# Kasli-SOC_MUX_I2C.net
KiCad netlist of a schematic drawn in Altium Designer
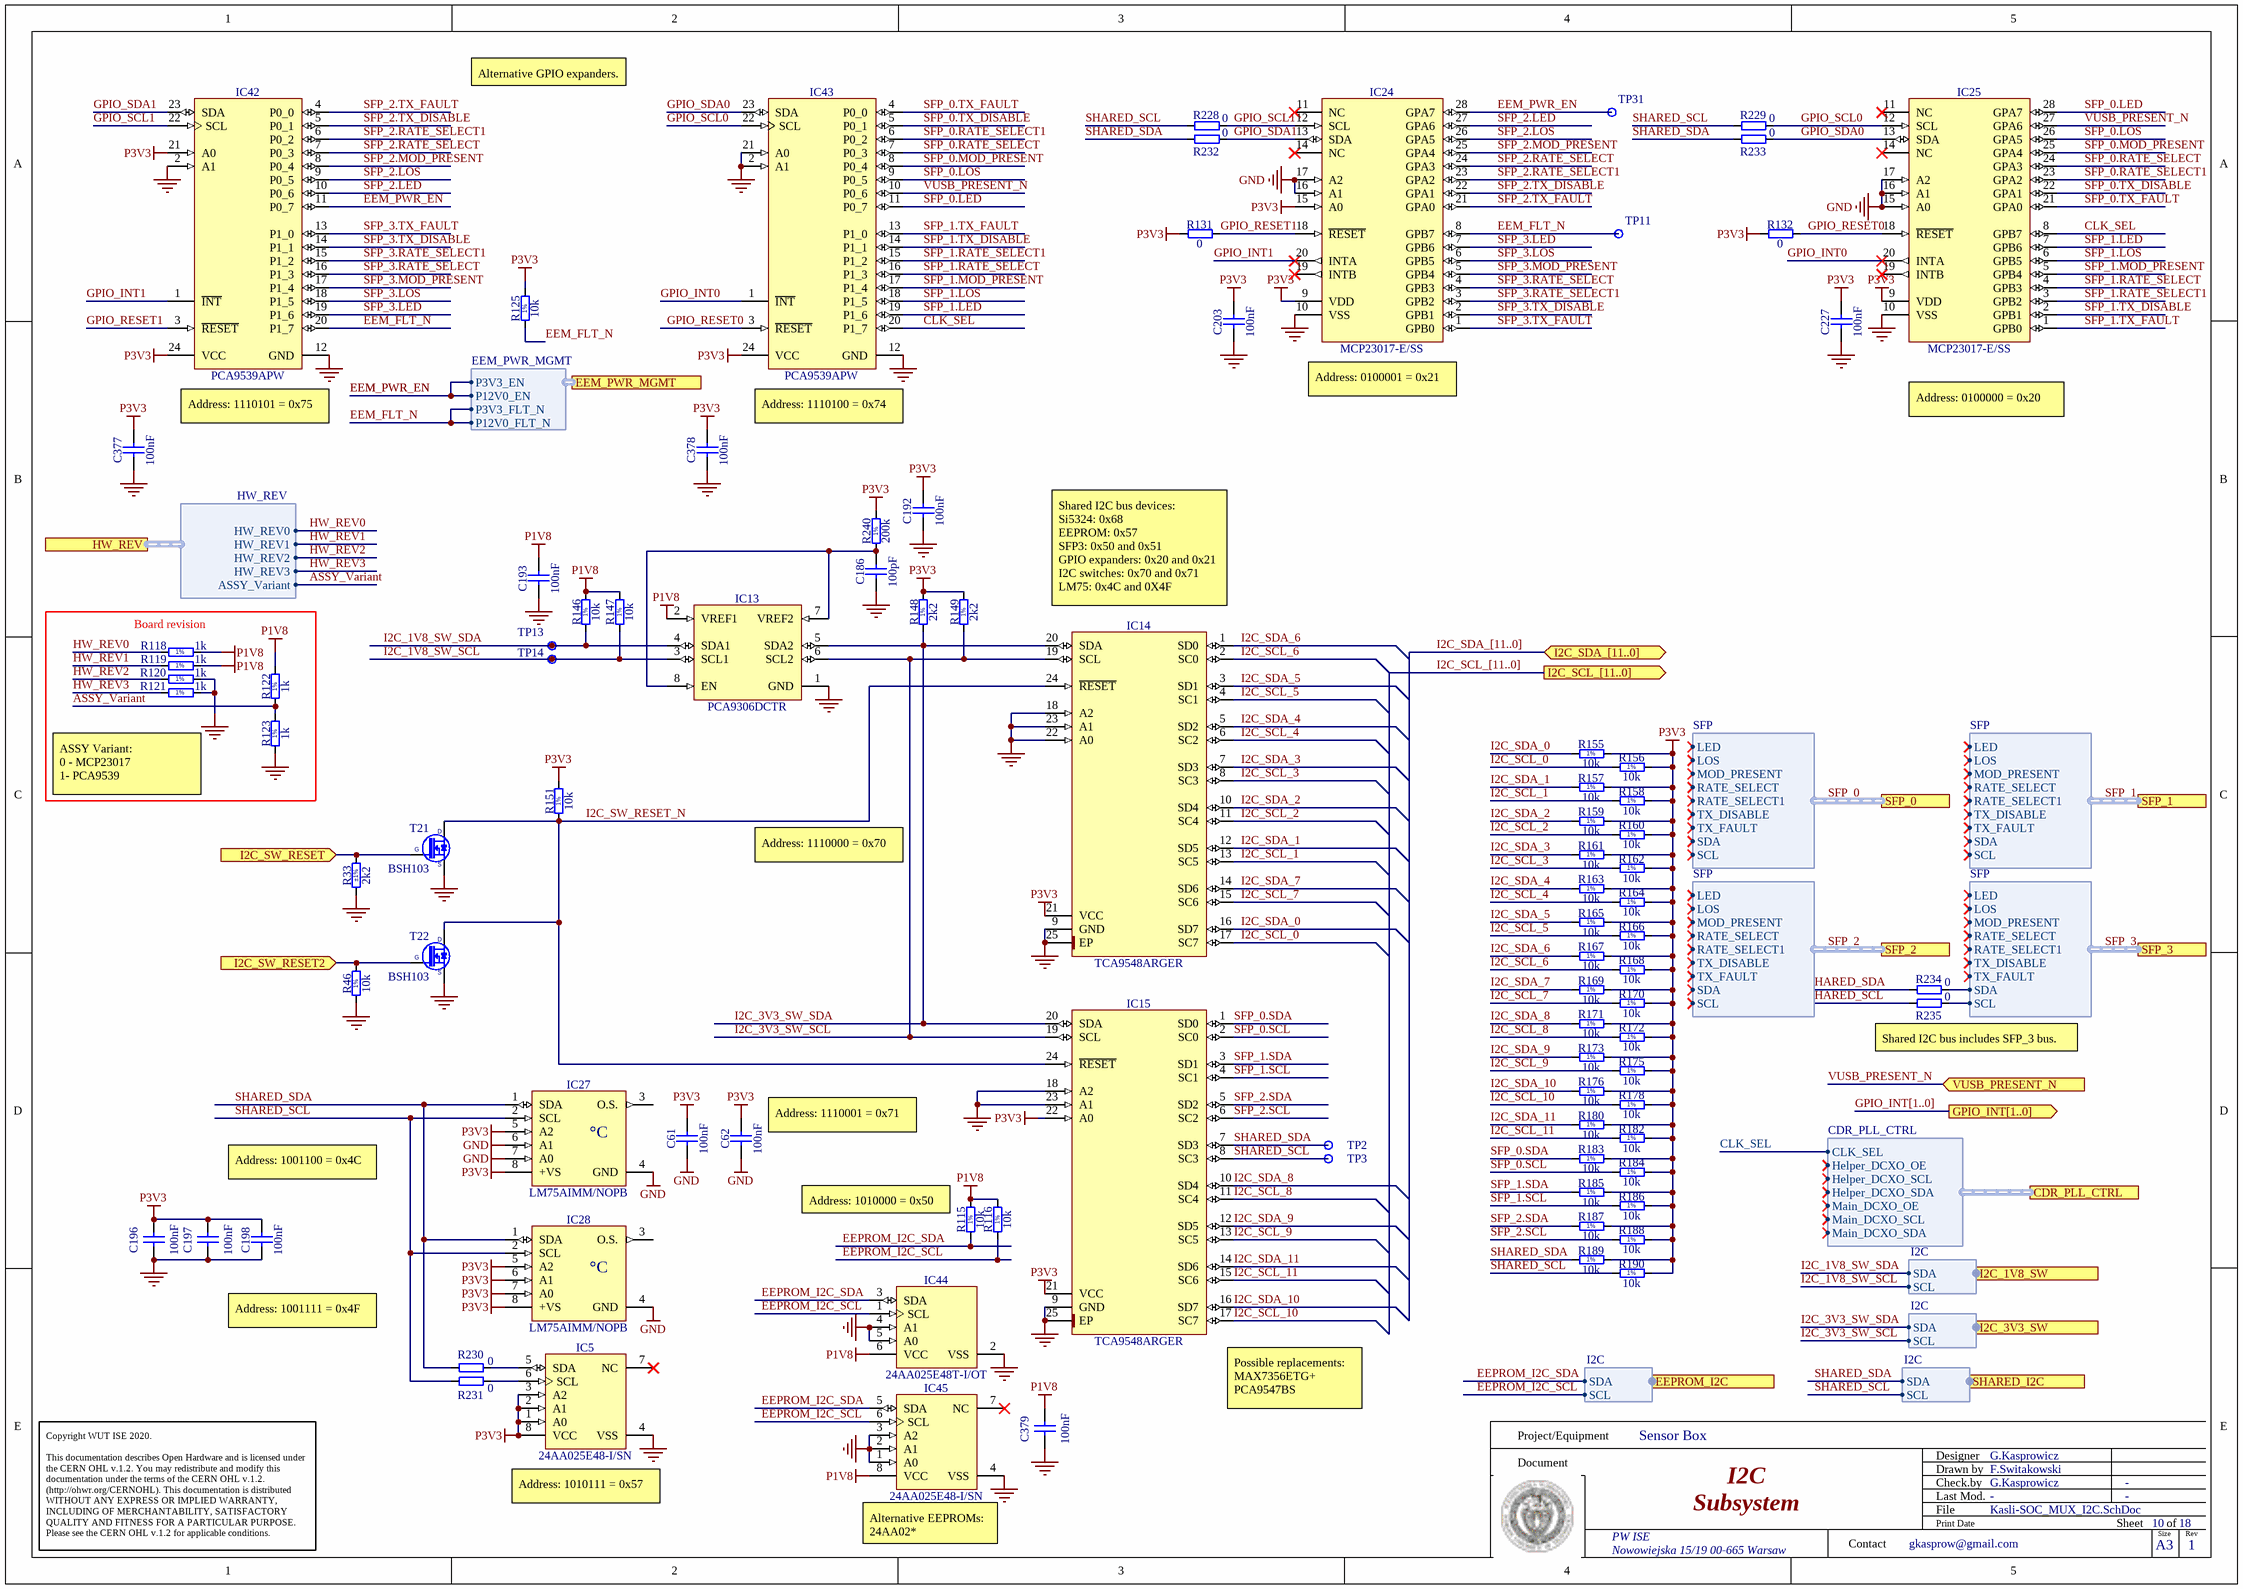
[diagram p0: Kasli-SOC_MUX_I2C.SchDoc]

(export (version "E")
  (design (tool "Eeschema 10.0.6"))
  (components
    (comp (ref "C61")
      (value "100nF")
      (footprint "CAPC1005X55N")
      (description "Non-polarised capacitor")
      (fields
        (field (name "PART NUMBER") "CC0402_100NF_16V_10%_X7R")
        (field (name "VOLTAGE") "16V")
        (field (name "AUTHOR") "CERN DEM JLC")
      )
      (libsource (lib "Capacitors") (part "Capacitor - non polarized"))
    )
    (comp (ref "C62")
      (value "100nF")
      (footprint "CAPC1005X55N")
      (description "Non-polarised capacitor")
      (fields
        (field (name "PART NUMBER") "CC0402_100NF_16V_10%_X7R")
        (field (name "VOLTAGE") "16V")
        (field (name "AUTHOR") "CERN DEM JLC")
      )
      (libsource (lib "Capacitors") (part "Capacitor - non polarized"))
    )
    (comp (ref "C186")
      (value "100pF")
      (footprint "CAPC1005X55N")
      (description "Non-polarised capacitor")
      (fields
        (field (name "PART NUMBER") "CC0402_100PF_50V_5%_C0G")
        (field (name "VOLTAGE") "50V")
        (field (name "AUTHOR") "CERN DEM JLC")
      )
      (libsource (lib "Capacitors") (part "Capacitor - non polarized"))
    )
    (comp (ref "C192")
      (value "100nF")
      (footprint "CAPC1005X55N")
      (description "Non-polarised capacitor")
      (fields
        (field (name "PART NUMBER") "CC0402_100NF_16V_10%_X7R")
        (field (name "VOLTAGE") "16V")
        (field (name "AUTHOR") "CERN DEM JLC")
      )
      (libsource (lib "Capacitors") (part "Capacitor - non polarized"))
    )
    (comp (ref "C193")
      (value "100nF")
      (footprint "CAPC1005X55N")
      (description "Non-polarised capacitor")
      (fields
        (field (name "PART NUMBER") "CC0402_100NF_16V_10%_X7R")
        (field (name "VOLTAGE") "16V")
        (field (name "AUTHOR") "CERN DEM JLC")
      )
      (libsource (lib "Capacitors") (part "Capacitor - non polarized"))
    )
    (comp (ref "C196")
      (value "100nF")
      (footprint "CAPC0603X33N")
      (description "Non-polarised capacitor")
      (fields
        (field (name "PART NUMBER") "CC0201_100NF_6.3V_10%_X5R")
        (field (name "VOLTAGE") "6.3V")
        (field (name "AUTHOR") "CERN DEM JLC")
      )
      (libsource (lib "Capacitors") (part "Capacitor - non polarized"))
    )
    (comp (ref "C197")
      (value "100nF")
      (footprint "CAPC0603X33N")
      (description "Non-polarised capacitor")
      (fields
        (field (name "PART NUMBER") "CC0201_100NF_6.3V_10%_X5R")
        (field (name "VOLTAGE") "6.3V")
        (field (name "AUTHOR") "CERN DEM JLC")
      )
      (libsource (lib "Capacitors") (part "Capacitor - non polarized"))
    )
    (comp (ref "C198")
      (value "100nF")
      (footprint "CAPC1005X55N")
      (description "Non-polarised capacitor")
      (fields
        (field (name "PART NUMBER") "CC0402_100NF_16V_10%_X7R")
        (field (name "VOLTAGE") "16V")
        (field (name "AUTHOR") "CERN DEM JLC")
      )
      (libsource (lib "Capacitors") (part "Capacitor - non polarized"))
    )
    (comp (ref "C203")
      (value "100nF")
      (footprint "CAPC1005X55N")
      (description "Non-polarised capacitor")
      (fields
        (field (name "PART NUMBER") "CC0402_100NF_16V_10%_X7R")
        (field (name "VOLTAGE") "16V")
        (field (name "AUTHOR") "CERN DEM JLC")
      )
      (libsource (lib "Capacitors") (part "Capacitor - non polarized"))
    )
    (comp (ref "C227")
      (value "100nF")
      (footprint "CAPC1005X55N")
      (description "Non-polarised capacitor")
      (fields
        (field (name "PART NUMBER") "CC0402_100NF_16V_10%_X7R")
        (field (name "VOLTAGE") "16V")
        (field (name "AUTHOR") "CERN DEM JLC")
      )
      (libsource (lib "Capacitors") (part "Capacitor - non polarized"))
    )
    (comp (ref "C377")
      (value "100nF")
      (footprint "CAPC1005X55N")
      (description "Non-polarised capacitor")
      (fields
        (field (name "PART NUMBER") "CC0402_100NF_16V_10%_X7R")
        (field (name "VOLTAGE") "16V")
        (field (name "AUTHOR") "CERN DEM JLC")
      )
      (libsource (lib "Capacitors") (part "Capacitor - non polarized"))
    )
    (comp (ref "C378")
      (value "100nF")
      (footprint "CAPC1005X55N")
      (description "Non-polarised capacitor")
      (fields
        (field (name "PART NUMBER") "CC0402_100NF_16V_10%_X7R")
        (field (name "VOLTAGE") "16V")
        (field (name "AUTHOR") "CERN DEM JLC")
      )
      (libsource (lib "Capacitors") (part "Capacitor - non polarized"))
    )
    (comp (ref "C379")
      (value "100nF")
      (footprint "CAPC1005X55N")
      (description "Non-polarised capacitor")
      (fields
        (field (name "PART NUMBER") "CC0402_100NF_16V_10%_X5R")
        (field (name "VOLTAGE") "16V")
        (field (name "AUTHOR") "CERN DEM JLC")
      )
      (libsource (lib "Capacitors") (part "Capacitor - non polarized"))
    )
    (comp (ref "IC5")
      (value "24AA025E48-I/SN")
      (footprint "SOIC127P600X175-8N")
      (description "1.7V-5.5V, 2K I2C™ Serial EEPROMs with EUI-48™ Node Identity")
      (fields (field (name "MANUFACTURER") "MICROCHIP TECHNOLOGY") (field (name "AUTHOR") "CERN DEM MR"))
      (libsource (lib "ICs And Semiconductors") (part "24AA025E48-I/SN"))
    )
    (comp (ref "IC13")
      (value "PCA9306DCTR")
      (footprint "SOP65P400X130-8N")
      (description "Dual Bidirectional I2C Bus And SMBus Voltage-Level Translator")
      (fields (field (name "MANUFACTURER") "TEXAS INSTRUMENTS") (field (name "AUTHOR") "CERN DEM JLC"))
      (libsource (lib "ICs And Semiconductors") (part "PCA9306D"))
    )
    (comp (ref "IC14")
      (value "TCA9548ARGER")
      (footprint "QFN50P400X400X100-25N-S220")
      (description "Low Voltage 8-Channel I2C Switch With Reset")
      (fields (field (name "MANUFACTURER") "TEXAS INSTRUMENTS") (field (name "AUTHOR") "CERN DEM JLC"))
      (libsource (lib "ICs And Semiconductors") (part "TCA9548ARGER"))
    )
    (comp (ref "IC15")
      (value "TCA9548ARGER")
      (footprint "QFN50P400X400X100-25N-S220")
      (description "Low Voltage 8-Channel I2C Switch With Reset")
      (fields (field (name "MANUFACTURER") "TEXAS INSTRUMENTS") (field (name "AUTHOR") "CERN DEM JLC"))
      (libsource (lib "ICs And Semiconductors") (part "TCA9548ARGER"))
    )
    (comp (ref "IC24")
      (value "MCP23017-E/SS")
      (footprint "SOP65P780X200-28N")
      (description "16-bit I/O Port Expander With Serial Interface")
      (fields (field (name "MANUFACTURER") "MICROCHIP TECHNOLOGY") (field (name "AUTHOR") "CERN DEM JLC"))
      (libsource (lib "ICs And Semiconductors") (part "MCP23017-E/SS"))
    )
    (comp (ref "IC25")
      (value "MCP23017-E/SS")
      (footprint "SOP65P780X200-28N")
      (description "16-bit I/O Port Expander With Serial Interface")
      (fields (field (name "MANUFACTURER") "MICROCHIP TECHNOLOGY") (field (name "AUTHOR") "CERN DEM JLC"))
      (libsource (lib "ICs And Semiconductors") (part "MCP23017-E/SS"))
    )
    (comp (ref "IC27")
      (value "LM75AIMM/NOPB")
      (footprint "SOP65P490X109-8N")
      (description "Digital Temperature Sensor and Thermal Watchdog with Two-Wire Interface")
      (fields (field (name "MANUFACTURER") "TEXAS INSTRUMENTS") (field (name "AUTHOR") "CERN DEM JLC"))
      (libsource (lib "ICs And Semiconductors") (part "LM75"))
    )
    (comp (ref "IC28")
      (value "LM75AIMM/NOPB")
      (footprint "SOP65P490X109-8N")
      (description "Digital Temperature Sensor and Thermal Watchdog with Two-Wire Interface")
      (fields (field (name "MANUFACTURER") "TEXAS INSTRUMENTS") (field (name "AUTHOR") "CERN DEM JLC"))
      (libsource (lib "ICs And Semiconductors") (part "LM75"))
    )
    (comp (ref "IC42")
      (value "PCA9539APW")
      (footprint "SOP65P640X110-24N")
      (description "Low-Voltage 16-Bit I2C-Bus I/O Port with Interrupt and Reset")
      (fields (field (name "MANUFACTURER") "NXP SEMICONDUCTORS") (field (name "AUTHOR") "CERN DEM JMW"))
      (libsource (lib "ICs And Semiconductors") (part "PCA9539APW"))
    )
    (comp (ref "IC43")
      (value "PCA9539APW")
      (footprint "SOP65P640X110-24N")
      (description "Low-Voltage 16-Bit I2C-Bus I/O Port with Interrupt and Reset")
      (fields (field (name "MANUFACTURER") "NXP SEMICONDUCTORS") (field (name "AUTHOR") "CERN DEM JMW"))
      (libsource (lib "ICs And Semiconductors") (part "PCA9539APW"))
    )
    (comp (ref "IC44")
      (value "24AA025E48T-I/OT")
      (footprint "SOT95P280X145-6N")
      (description "1.7V-5.5V, 2K I2C Serial EEPROM With EUI-48 Node Identity")
      (fields (field (name "MANUFACTURER") "MICROCHIP TECHNOLOGY") (field (name "AUTHOR") "CERN DEM BC"))
      (libsource (lib "ICs And Semiconductors") (part "24AA025E48T-I/OT"))
    )
    (comp (ref "IC45")
      (value "24AA025E48-I/SN")
      (footprint "SOIC127P600X175-8N")
      (description "1.7V-5.5V, 2K I2C™ Serial EEPROMs with EUI-48™ Node Identity")
      (fields (field (name "MANUFACTURER") "MICROCHIP TECHNOLOGY") (field (name "AUTHOR") "CERN DEM MR"))
      (libsource (lib "ICs And Semiconductors") (part "24AA025E48-I/SN"))
    )
    (comp (ref "R33")
      (value "2k2")
      (footprint "RESC1005X40N")
      (description "Resistor - 1%")
      (fields
        (field (name "TOLERANCE") "±1%")
        (field (name "PART NUMBER") "R0402_2K2_1%_0.0625W_100PPM")
        (field (name "POWER") "0.0625W")
        (field (name "AUTHOR") "CERN DEM JLC")
      )
      (libsource (lib "Resistors") (part "Resistor - 1%"))
    )
    (comp (ref "R46")
      (value "10k")
      (footprint "RESC1005X40N")
      (description "Resistor - 1%")
      (fields
        (field (name "PART NUMBER") "R0402_10K_1%_0.0625W_100PPM")
        (field (name "POWER") "0.0625W")
        (field (name "AUTHOR") "CERN DEM JLC")
      )
      (libsource (lib "Resistors") (part "Resistor - 1%"))
    )
    (comp (ref "R115")
      (value "10k")
      (footprint "RESC1005X40N")
      (description "Resistor - 1%")
      (fields
        (field (name "PART NUMBER") "R0402_10K_1%_0.0625W_100PPM")
        (field (name "POWER") "0.0625W")
        (field (name "AUTHOR") "CERN DEM JLC")
      )
      (libsource (lib "Resistors") (part "Resistor - 1%"))
    )
    (comp (ref "R116")
      (value "10k")
      (footprint "RESC1005X40N")
      (description "Resistor - 1%")
      (fields
        (field (name "PART NUMBER") "R0402_10K_1%_0.0625W_100PPM")
        (field (name "POWER") "0.0625W")
        (field (name "AUTHOR") "CERN DEM JLC")
      )
      (libsource (lib "Resistors") (part "Resistor - 1%"))
    )
    (comp (ref "R118")
      (value "1k")
      (footprint "RESC1005X40N")
      (description "Resistor - 1%")
      (fields
        (field (name "PART NUMBER") "R0402_1K_1%_0.0625W_100PPM")
        (field (name "POWER") "0.0625W")
        (field (name "AUTHOR") "CERN DEM JLC")
      )
      (libsource (lib "Resistors") (part "Resistor - 1%"))
    )
    (comp (ref "R119")
      (value "1k")
      (footprint "RESC1005X40N")
      (description "Resistor - 1%")
      (fields
        (field (name "PART NUMBER") "R0402_1K_1%_0.0625W_100PPM")
        (field (name "POWER") "0.0625W")
        (field (name "AUTHOR") "CERN DEM JLC")
      )
      (libsource (lib "Resistors") (part "Resistor - 1%"))
    )
    (comp (ref "R120")
      (value "1k")
      (footprint "RESC1005X40N")
      (description "Resistor - 1%")
      (fields
        (field (name "PART NUMBER") "R0402_1K_1%_0.0625W_100PPM")
        (field (name "POWER") "0.0625W")
        (field (name "AUTHOR") "CERN DEM JLC")
      )
      (libsource (lib "Resistors") (part "Resistor - 1%"))
    )
    (comp (ref "R121")
      (value "1k")
      (footprint "RESC1005X40N")
      (description "Resistor - 1%")
      (fields
        (field (name "PART NUMBER") "R0402_1K_1%_0.0625W_100PPM")
        (field (name "POWER") "0.0625W")
        (field (name "AUTHOR") "CERN DEM JLC")
      )
      (libsource (lib "Resistors") (part "Resistor - 1%"))
    )
    (comp (ref "R122")
      (value "1k")
      (footprint "RESC1005X40N")
      (description "Resistor - 1%")
      (fields
        (field (name "PART NUMBER") "R0402_1K_1%_0.0625W_100PPM")
        (field (name "POWER") "0.0625W")
        (field (name "AUTHOR") "CERN DEM JLC")
      )
      (libsource (lib "Resistors") (part "Resistor - 1%"))
    )
    (comp (ref "R123")
      (value "1k")
      (footprint "RESC1005X40N")
      (description "Resistor - 1%")
      (fields
        (field (name "PART NUMBER") "R0402_1K_1%_0.0625W_100PPM")
        (field (name "POWER") "0.0625W")
        (field (name "AUTHOR") "CERN DEM JLC")
      )
      (libsource (lib "Resistors") (part "Resistor - 1%"))
    )
    (comp (ref "R125")
      (value "10k")
      (footprint "RESC1005X40N")
      (description "Resistor - 1%")
      (fields
        (field (name "PART NUMBER") "R0402_10K_1%_0.0625W_100PPM")
        (field (name "POWER") "0.0625W")
        (field (name "AUTHOR") "CERN DEM JLC")
      )
      (libsource (lib "Resistors") (part "Resistor - 1%"))
    )
    (comp (ref "R131")
      (value "0")
      (footprint "RESC1005X40N")
      (description "Resistor")
      (fields
        (field (name "PART NUMBER") "R0402_0R_JUMPER")
        (field (name "MANUFACTURER") "GENERIC")
        (field (name "AUTHOR") "CERN DEM JLC")
      )
      (libsource (lib "Resistors") (part "Resistor"))
    )
    (comp (ref "R132")
      (value "0")
      (footprint "RESC1005X40N")
      (description "Resistor")
      (fields
        (field (name "PART NUMBER") "R0402_0R_JUMPER")
        (field (name "MANUFACTURER") "GENERIC")
        (field (name "AUTHOR") "CERN DEM JLC")
      )
      (libsource (lib "Resistors") (part "Resistor"))
    )
    (comp (ref "R146")
      (value "10k")
      (footprint "RESC1005X40N")
      (description "Resistor - 1%")
      (fields
        (field (name "PART NUMBER") "R0402_10K_1%_0.0625W_100PPM")
        (field (name "POWER") "0.0625W")
        (field (name "AUTHOR") "CERN DEM JLC")
      )
      (libsource (lib "Resistors") (part "Resistor - 1%"))
    )
    (comp (ref "R147")
      (value "10k")
      (footprint "RESC1005X40N")
      (description "Resistor - 1%")
      (fields
        (field (name "PART NUMBER") "R0402_10K_1%_0.0625W_100PPM")
        (field (name "POWER") "0.0625W")
        (field (name "AUTHOR") "CERN DEM JLC")
      )
      (libsource (lib "Resistors") (part "Resistor - 1%"))
    )
    (comp (ref "R148")
      (value "2k2")
      (footprint "RESC1005X40N")
      (description "Resistor - 1%")
      (fields
        (field (name "PART NUMBER") "R0402_2K2_1%_0.0625W_100PPM")
        (field (name "POWER") "0.0625W")
        (field (name "AUTHOR") "CERN DEM JLC")
      )
      (libsource (lib "Resistors") (part "Resistor - 1%"))
    )
    (comp (ref "R149")
      (value "2k2")
      (footprint "RESC1005X40N")
      (description "Resistor - 1%")
      (fields
        (field (name "PART NUMBER") "R0402_2K2_1%_0.0625W_100PPM")
        (field (name "POWER") "0.0625W")
        (field (name "AUTHOR") "CERN DEM JLC")
      )
      (libsource (lib "Resistors") (part "Resistor - 1%"))
    )
    (comp (ref "R151")
      (value "10k")
      (footprint "RESC1005X40N")
      (description "Resistor - 1%")
      (fields
        (field (name "PART NUMBER") "R0402_10K_1%_0.0625W_100PPM")
        (field (name "POWER") "0.0625W")
        (field (name "AUTHOR") "CERN DEM JLC")
      )
      (libsource (lib "Resistors") (part "Resistor - 1%"))
    )
    (comp (ref "R155")
      (value "10k")
      (footprint "RESC1005X40N")
      (description "Resistor - 1%")
      (fields
        (field (name "PART NUMBER") "R0402_10K_1%_0.0625W_100PPM")
        (field (name "POWER") "0.0625W")
        (field (name "AUTHOR") "CERN DEM JLC")
      )
      (libsource (lib "Resistors") (part "Resistor - 1%"))
    )
    (comp (ref "R156")
      (value "10k")
      (footprint "RESC1005X40N")
      (description "Resistor - 1%")
      (fields
        (field (name "PART NUMBER") "R0402_10K_1%_0.0625W_100PPM")
        (field (name "POWER") "0.0625W")
        (field (name "AUTHOR") "CERN DEM JLC")
      )
      (libsource (lib "Resistors") (part "Resistor - 1%"))
    )
    (comp (ref "R157")
      (value "10k")
      (footprint "RESC1005X40N")
      (description "Resistor - 1%")
      (fields
        (field (name "PART NUMBER") "R0402_10K_1%_0.0625W_100PPM")
        (field (name "POWER") "0.0625W")
        (field (name "AUTHOR") "CERN DEM JLC")
      )
      (libsource (lib "Resistors") (part "Resistor - 1%"))
    )
    (comp (ref "R158")
      (value "10k")
      (footprint "RESC1005X40N")
      (description "Resistor - 1%")
      (fields
        (field (name "PART NUMBER") "R0402_10K_1%_0.0625W_100PPM")
        (field (name "POWER") "0.0625W")
        (field (name "AUTHOR") "CERN DEM JLC")
      )
      (libsource (lib "Resistors") (part "Resistor - 1%"))
    )
    (comp (ref "R159")
      (value "10k")
      (footprint "RESC1005X40N")
      (description "Resistor - 1%")
      (fields
        (field (name "PART NUMBER") "R0402_10K_1%_0.0625W_100PPM")
        (field (name "POWER") "0.0625W")
        (field (name "AUTHOR") "CERN DEM JLC")
      )
      (libsource (lib "Resistors") (part "Resistor - 1%"))
    )
    (comp (ref "R160")
      (value "10k")
      (footprint "RESC1005X40N")
      (description "Resistor - 1%")
      (fields
        (field (name "PART NUMBER") "R0402_10K_1%_0.0625W_100PPM")
        (field (name "POWER") "0.0625W")
        (field (name "AUTHOR") "CERN DEM JLC")
      )
      (libsource (lib "Resistors") (part "Resistor - 1%"))
    )
    (comp (ref "R161")
      (value "10k")
      (footprint "RESC1005X40N")
      (description "Resistor - 1%")
      (fields
        (field (name "PART NUMBER") "R0402_10K_1%_0.0625W_100PPM")
        (field (name "POWER") "0.0625W")
        (field (name "AUTHOR") "CERN DEM JLC")
      )
      (libsource (lib "Resistors") (part "Resistor - 1%"))
    )
    (comp (ref "R162")
      (value "10k")
      (footprint "RESC1005X40N")
      (description "Resistor - 1%")
      (fields
        (field (name "PART NUMBER") "R0402_10K_1%_0.0625W_100PPM")
        (field (name "POWER") "0.0625W")
        (field (name "AUTHOR") "CERN DEM JLC")
      )
      (libsource (lib "Resistors") (part "Resistor - 1%"))
    )
    (comp (ref "R163")
      (value "10k")
      (footprint "RESC1005X40N")
      (description "Resistor - 1%")
      (fields
        (field (name "PART NUMBER") "R0402_10K_1%_0.0625W_100PPM")
        (field (name "POWER") "0.0625W")
        (field (name "AUTHOR") "CERN DEM JLC")
      )
      (libsource (lib "Resistors") (part "Resistor - 1%"))
    )
    (comp (ref "R164")
      (value "10k")
      (footprint "RESC1005X40N")
      (description "Resistor - 1%")
      (fields
        (field (name "PART NUMBER") "R0402_10K_1%_0.0625W_100PPM")
        (field (name "POWER") "0.0625W")
        (field (name "AUTHOR") "CERN DEM JLC")
      )
      (libsource (lib "Resistors") (part "Resistor - 1%"))
    )
    (comp (ref "R165")
      (value "10k")
      (footprint "RESC1005X40N")
      (description "Resistor - 1%")
      (fields
        (field (name "PART NUMBER") "R0402_10K_1%_0.0625W_100PPM")
        (field (name "POWER") "0.0625W")
        (field (name "AUTHOR") "CERN DEM JLC")
      )
      (libsource (lib "Resistors") (part "Resistor - 1%"))
    )
    (comp (ref "R166")
      (value "10k")
      (footprint "RESC1005X40N")
      (description "Resistor - 1%")
      (fields
        (field (name "PART NUMBER") "R0402_10K_1%_0.0625W_100PPM")
        (field (name "POWER") "0.0625W")
        (field (name "AUTHOR") "CERN DEM JLC")
      )
      (libsource (lib "Resistors") (part "Resistor - 1%"))
    )
    (comp (ref "R167")
      (value "10k")
      (footprint "RESC1005X40N")
      (description "Resistor - 1%")
      (fields
        (field (name "PART NUMBER") "R0402_10K_1%_0.0625W_100PPM")
        (field (name "POWER") "0.0625W")
        (field (name "AUTHOR") "CERN DEM JLC")
      )
      (libsource (lib "Resistors") (part "Resistor - 1%"))
    )
    (comp (ref "R168")
      (value "10k")
      (footprint "RESC1005X40N")
      (description "Resistor - 1%")
      (fields
        (field (name "PART NUMBER") "R0402_10K_1%_0.0625W_100PPM")
        (field (name "POWER") "0.0625W")
        (field (name "AUTHOR") "CERN DEM JLC")
      )
      (libsource (lib "Resistors") (part "Resistor - 1%"))
    )
    (comp (ref "R169")
      (value "10k")
      (footprint "RESC1005X40N")
      (description "Resistor - 1%")
      (fields
        (field (name "PART NUMBER") "R0402_10K_1%_0.0625W_100PPM")
        (field (name "POWER") "0.0625W")
        (field (name "AUTHOR") "CERN DEM JLC")
      )
      (libsource (lib "Resistors") (part "Resistor - 1%"))
    )
    (comp (ref "R170")
      (value "10k")
      (footprint "RESC1005X40N")
      (description "Resistor - 1%")
      (fields
        (field (name "PART NUMBER") "R0402_10K_1%_0.0625W_100PPM")
        (field (name "POWER") "0.0625W")
        (field (name "AUTHOR") "CERN DEM JLC")
      )
      (libsource (lib "Resistors") (part "Resistor - 1%"))
    )
    (comp (ref "R171")
      (value "10k")
      (footprint "RESC1005X40N")
      (description "Resistor - 1%")
      (fields
        (field (name "PART NUMBER") "R0402_10K_1%_0.0625W_100PPM")
        (field (name "POWER") "0.0625W")
        (field (name "AUTHOR") "CERN DEM JLC")
      )
      (libsource (lib "Resistors") (part "Resistor - 1%"))
    )
    (comp (ref "R172")
      (value "10k")
      (footprint "RESC1005X40N")
      (description "Resistor - 1%")
      (fields
        (field (name "PART NUMBER") "R0402_10K_1%_0.0625W_100PPM")
        (field (name "POWER") "0.0625W")
        (field (name "AUTHOR") "CERN DEM JLC")
      )
      (libsource (lib "Resistors") (part "Resistor - 1%"))
    )
    (comp (ref "R173")
      (value "10k")
      (footprint "RESC1005X40N")
      (description "Resistor - 1%")
      (fields
        (field (name "PART NUMBER") "R0402_10K_1%_0.0625W_100PPM")
        (field (name "POWER") "0.0625W")
        (field (name "AUTHOR") "CERN DEM JLC")
      )
      (libsource (lib "Resistors") (part "Resistor - 1%"))
    )
    (comp (ref "R175")
      (value "10k")
      (footprint "RESC1005X40N")
      (description "Resistor - 1%")
      (fields
        (field (name "PART NUMBER") "R0402_10K_1%_0.0625W_100PPM")
        (field (name "POWER") "0.0625W")
        (field (name "AUTHOR") "CERN DEM JLC")
      )
      (libsource (lib "Resistors") (part "Resistor - 1%"))
    )
    (comp (ref "R176")
      (value "10k")
      (footprint "RESC1005X40N")
      (description "Resistor - 1%")
      (fields
        (field (name "PART NUMBER") "R0402_10K_1%_0.0625W_100PPM")
        (field (name "POWER") "0.0625W")
        (field (name "AUTHOR") "CERN DEM JLC")
      )
      (libsource (lib "Resistors") (part "Resistor - 1%"))
    )
    (comp (ref "R178")
      (value "10k")
      (footprint "RESC1005X40N")
      (description "Resistor - 1%")
      (fields
        (field (name "PART NUMBER") "R0402_10K_1%_0.0625W_100PPM")
        (field (name "POWER") "0.0625W")
        (field (name "AUTHOR") "CERN DEM JLC")
      )
      (libsource (lib "Resistors") (part "Resistor - 1%"))
    )
    (comp (ref "R180")
      (value "10k")
      (footprint "RESC1005X40N")
      (description "Resistor - 1%")
      (fields
        (field (name "PART NUMBER") "R0402_10K_1%_0.0625W_100PPM")
        (field (name "POWER") "0.0625W")
        (field (name "AUTHOR") "CERN DEM JLC")
      )
      (libsource (lib "Resistors") (part "Resistor - 1%"))
    )
    (comp (ref "R182")
      (value "10k")
      (footprint "RESC1005X40N")
      (description "Resistor - 1%")
      (fields
        (field (name "PART NUMBER") "R0402_10K_1%_0.0625W_100PPM")
        (field (name "POWER") "0.0625W")
        (field (name "AUTHOR") "CERN DEM JLC")
      )
      (libsource (lib "Resistors") (part "Resistor - 1%"))
    )
    (comp (ref "R183")
      (value "10k")
      (footprint "RESC1005X40N")
      (description "Resistor - 1%")
      (fields
        (field (name "PART NUMBER") "R0402_10K_1%_0.0625W_100PPM")
        (field (name "POWER") "0.0625W")
        (field (name "AUTHOR") "CERN DEM JLC")
      )
      (libsource (lib "Resistors") (part "Resistor - 1%"))
    )
    (comp (ref "R184")
      (value "10k")
      (footprint "RESC1005X40N")
      (description "Resistor - 1%")
      (fields
        (field (name "PART NUMBER") "R0402_10K_1%_0.0625W_100PPM")
        (field (name "POWER") "0.0625W")
        (field (name "AUTHOR") "CERN DEM JLC")
      )
      (libsource (lib "Resistors") (part "Resistor - 1%"))
    )
    (comp (ref "R185")
      (value "10k")
      (footprint "RESC1005X40N")
      (description "Resistor - 1%")
      (fields
        (field (name "PART NUMBER") "R0402_10K_1%_0.0625W_100PPM")
        (field (name "POWER") "0.0625W")
        (field (name "AUTHOR") "CERN DEM JLC")
      )
      (libsource (lib "Resistors") (part "Resistor - 1%"))
    )
    (comp (ref "R186")
      (value "10k")
      (footprint "RESC1005X40N")
      (description "Resistor - 1%")
      (fields
        (field (name "PART NUMBER") "R0402_10K_1%_0.0625W_100PPM")
        (field (name "POWER") "0.0625W")
        (field (name "AUTHOR") "CERN DEM JLC")
      )
      (libsource (lib "Resistors") (part "Resistor - 1%"))
    )
    (comp (ref "R187")
      (value "10k")
      (footprint "RESC1005X40N")
      (description "Resistor - 1%")
      (fields
        (field (name "PART NUMBER") "R0402_10K_1%_0.0625W_100PPM")
        (field (name "POWER") "0.0625W")
        (field (name "AUTHOR") "CERN DEM JLC")
      )
      (libsource (lib "Resistors") (part "Resistor - 1%"))
    )
    (comp (ref "R188")
      (value "10k")
      (footprint "RESC1005X40N")
      (description "Resistor - 1%")
      (fields
        (field (name "PART NUMBER") "R0402_10K_1%_0.0625W_100PPM")
        (field (name "POWER") "0.0625W")
        (field (name "AUTHOR") "CERN DEM JLC")
      )
      (libsource (lib "Resistors") (part "Resistor - 1%"))
    )
    (comp (ref "R189")
      (value "10k")
      (footprint "RESC1005X40N")
      (description "Resistor - 1%")
      (fields
        (field (name "PART NUMBER") "R0402_10K_1%_0.0625W_100PPM")
        (field (name "POWER") "0.0625W")
        (field (name "AUTHOR") "CERN DEM JLC")
      )
      (libsource (lib "Resistors") (part "Resistor - 1%"))
    )
    (comp (ref "R190")
      (value "10k")
      (footprint "RESC1005X40N")
      (description "Resistor - 1%")
      (fields
        (field (name "PART NUMBER") "R0402_10K_1%_0.0625W_100PPM")
        (field (name "POWER") "0.0625W")
        (field (name "AUTHOR") "CERN DEM JLC")
      )
      (libsource (lib "Resistors") (part "Resistor - 1%"))
    )
    (comp (ref "R228")
      (value "0")
      (footprint "RESC1005X40N")
      (description "Resistor")
      (fields
        (field (name "PART NUMBER") "R0402_0R_JUMPER")
        (field (name "MANUFACTURER") "GENERIC")
        (field (name "AUTHOR") "CERN DEM JLC")
      )
      (libsource (lib "Resistors") (part "Resistor"))
    )
    (comp (ref "R229")
      (value "0")
      (footprint "RESC1005X40N")
      (description "Resistor")
      (fields
        (field (name "PART NUMBER") "R0402_0R_JUMPER")
        (field (name "MANUFACTURER") "GENERIC")
        (field (name "AUTHOR") "CERN DEM JLC")
      )
      (libsource (lib "Resistors") (part "Resistor"))
    )
    (comp (ref "R230")
      (value "0")
      (footprint "RESC1005X40N")
      (description "Resistor")
      (fields
        (field (name "PART NUMBER") "R0402_0R_JUMPER")
        (field (name "MANUFACTURER") "GENERIC")
        (field (name "AUTHOR") "CERN DEM JLC")
      )
      (libsource (lib "Resistors") (part "Resistor"))
    )
    (comp (ref "R231")
      (value "0")
      (footprint "RESC1005X40N")
      (description "Resistor")
      (fields
        (field (name "PART NUMBER") "R0402_0R_JUMPER")
        (field (name "MANUFACTURER") "GENERIC")
        (field (name "AUTHOR") "CERN DEM JLC")
      )
      (libsource (lib "Resistors") (part "Resistor"))
    )
    (comp (ref "R232")
      (value "0")
      (footprint "RESC1005X40N")
      (description "Resistor")
      (fields
        (field (name "PART NUMBER") "R0402_0R_JUMPER")
        (field (name "MANUFACTURER") "GENERIC")
        (field (name "AUTHOR") "CERN DEM JLC")
      )
      (libsource (lib "Resistors") (part "Resistor"))
    )
    (comp (ref "R233")
      (value "0")
      (footprint "RESC1005X40N")
      (description "Resistor")
      (fields
        (field (name "PART NUMBER") "R0402_0R_JUMPER")
        (field (name "MANUFACTURER") "GENERIC")
        (field (name "AUTHOR") "CERN DEM JLC")
      )
      (libsource (lib "Resistors") (part "Resistor"))
    )
    (comp (ref "R234")
      (value "0")
      (footprint "RESC1005X40N")
      (description "Resistor")
      (fields
        (field (name "PART NUMBER") "R0402_0R_JUMPER")
        (field (name "MANUFACTURER") "GENERIC")
        (field (name "AUTHOR") "CERN DEM JLC")
      )
      (libsource (lib "Resistors") (part "Resistor"))
    )
    (comp (ref "R235")
      (value "0")
      (footprint "RESC1005X40N")
      (description "Resistor")
      (fields
        (field (name "PART NUMBER") "R0402_0R_JUMPER")
        (field (name "MANUFACTURER") "GENERIC")
        (field (name "AUTHOR") "CERN DEM JLC")
      )
      (libsource (lib "Resistors") (part "Resistor"))
    )
    (comp (ref "R240")
      (value "200k")
      (footprint "RESC1005X40N")
      (description "Resistor - 1%")
      (fields
        (field (name "PART NUMBER") "R0402_200K_1%_0.0625W_100PPM")
        (field (name "POWER") "0.0625W")
        (field (name "AUTHOR") "CERN DEM JLC")
      )
      (libsource (lib "Resistors") (part "Resistor - 1%"))
    )
    (comp (ref "T21")
      (value "BSH103")
      (footprint "SOT95P230X110-3N")
      (description "N-CHANNEL MOSFET WITH DIODE")
      (fields (field (name "MANUFACTURER") "NEXPERIA") (field (name "AUTHOR") "CERN DEM JLC"))
      (libsource (lib "ICs And Semiconductors") (part "N-MOSFET-D 1G 2S 3D"))
    )
    (comp (ref "T22")
      (value "BSH103")
      (footprint "SOT95P230X110-3N")
      (description "N-CHANNEL MOSFET WITH DIODE")
      (fields (field (name "MANUFACTURER") "NEXPERIA") (field (name "AUTHOR") "CERN DEM JLC"))
      (libsource (lib "ICs And Semiconductors") (part "N-MOSFET-D 1G 2S 3D"))
    )
    (comp (ref "TP2")
      (value "Si5324 I2C SDA")
      (footprint "TPS127")
      (description "Test Point")
      (fields (field (name "PART NUMBER") "SMD_PAD_1.27X1.27MM") (field (name "AUTHOR") "CERN DEM JLC"))
      (libsource (lib "Eletro-mechanical") (part "Test Point"))
    )
    (comp (ref "TP3")
      (value "Si5324 I2C SCL")
      (footprint "TPS127")
      (description "Test Point")
      (fields (field (name "PART NUMBER") "SMD_PAD_1.27X1.27MM") (field (name "AUTHOR") "CERN DEM JLC"))
      (libsource (lib "Eletro-mechanical") (part "Test Point"))
    )
    (comp (ref "TP11")
      (value "I2C SW SCL")
      (footprint "TPS127")
      (description "Test Point")
      (fields (field (name "PART NUMBER") "SMD_PAD_1.27X1.27MM") (field (name "AUTHOR") "CERN DEM JLC"))
      (libsource (lib "Eletro-mechanical") (part "Test Point"))
    )
    (comp (ref "TP13")
      (value "I2C SW SDA")
      (footprint "TPS127")
      (description "Test Point")
      (fields (field (name "PART NUMBER") "SMD_PAD_1.27X1.27MM") (field (name "AUTHOR") "CERN DEM JLC"))
      (libsource (lib "Eletro-mechanical") (part "Test Point"))
    )
    (comp (ref "TP14")
      (value "I2C SW SCL")
      (footprint "TPS127")
      (description "Test Point")
      (fields (field (name "PART NUMBER") "SMD_PAD_1.27X1.27MM") (field (name "AUTHOR") "CERN DEM JLC"))
      (libsource (lib "Eletro-mechanical") (part "Test Point"))
    )
    (comp (ref "TP31")
      (value "I2C SW SCL")
      (footprint "TPS127")
      (description "Test Point")
      (fields (field (name "PART NUMBER") "SMD_PAD_1.27X1.27MM") (field (name "AUTHOR") "CERN DEM JLC"))
      (libsource (lib "Eletro-mechanical") (part "Test Point"))
    )
  )
  (nets
    (net (code "9") (name "/ASSY_Variant") (class "Default")
      (node (ref "R122") (pin "1") (pinfunction "1_1") (pintype "passive"))
      (node (ref "R123") (pin "2") (pinfunction "2_2") (pintype "passive"))
    )
    (net (code "10") (name "/CLK_SEL") (class "Default")
      (node (ref "IC25") (pin "8") (pinfunction "GPB7_8") (pintype "bidirectional"))
      (node (ref "IC43") (pin "20") (pinfunction "P1_7_20") (pintype "bidirectional"))
    )
    (net (code "11") (name "/EEM_FLT_N") (class "Default")
      (node (ref "IC24") (pin "8") (pinfunction "GPB7_8") (pintype "bidirectional"))
      (node (ref "IC42") (pin "20") (pinfunction "P1_7_20") (pintype "bidirectional"))
      (node (ref "R125") (pin "1") (pinfunction "1_1") (pintype "passive"))
      (node (ref "TP11") (pin "1") (pinfunction "1_1") (pintype "bidirectional"))
    )
    (net (code "12") (name "/EEM_PWR_EN") (class "Default")
      (node (ref "IC24") (pin "28") (pinfunction "GPA7_28") (pintype "bidirectional"))
      (node (ref "IC42") (pin "11") (pinfunction "P0_7_11") (pintype "bidirectional"))
      (node (ref "TP31") (pin "1") (pinfunction "1_1") (pintype "bidirectional"))
    )
    (net (code "13") (name "/EEPROM_I2C_SCL") (class "Default")
      (node (ref "IC44") (pin "1") (pinfunction "SCL_1") (pintype "input"))
      (node (ref "IC45") (pin "6") (pinfunction "SCL_6") (pintype "input"))
      (node (ref "R116") (pin "1") (pinfunction "1_1") (pintype "passive"))
    )
    (net (code "14") (name "/EEPROM_I2C_SDA") (class "Default")
      (node (ref "IC44") (pin "3") (pinfunction "SDA_3") (pintype "bidirectional"))
      (node (ref "IC45") (pin "5") (pinfunction "SDA_5") (pintype "bidirectional"))
      (node (ref "R115") (pin "1") (pinfunction "1_1") (pintype "passive"))
    )
    (net (code "15") (name "/GPIO_INT0") (class "Default")
      (node (ref "IC25") (pin "20") (pinfunction "INTA_20") (pintype "output"))
      (node (ref "IC43") (pin "1") (pinfunction "~{INT}_1") (pintype "open_collector"))
    )
    (net (code "16") (name "/GPIO_INT1") (class "Default")
      (node (ref "IC24") (pin "20") (pinfunction "INTA_20") (pintype "output"))
      (node (ref "IC42") (pin "1") (pinfunction "~{INT}_1") (pintype "open_collector"))
    )
    (net (code "18") (name "/GPIO_RESET0") (class "Default")
      (node (ref "IC25") (pin "18") (pinfunction "~{RESET}_18") (pintype "input"))
      (node (ref "IC43") (pin "3") (pinfunction "~{RESET}_3") (pintype "input"))
      (node (ref "R132") (pin "2") (pinfunction "2_2") (pintype "passive"))
    )
    (net (code "19") (name "/GPIO_RESET1") (class "Default")
      (node (ref "IC24") (pin "18") (pinfunction "~{RESET}_18") (pintype "input"))
      (node (ref "IC42") (pin "3") (pinfunction "~{RESET}_3") (pintype "input"))
      (node (ref "R131") (pin "2") (pinfunction "2_2") (pintype "passive"))
    )
    (net (code "20") (name "/GPIO_SCL0") (class "Default")
      (node (ref "IC25") (pin "12") (pinfunction "SCL_12") (pintype "input"))
      (node (ref "IC43") (pin "22") (pinfunction "SCL_22") (pintype "input"))
      (node (ref "R229") (pin "2") (pinfunction "2_2") (pintype "passive"))
    )
    (net (code "21") (name "/GPIO_SCL1") (class "Default")
      (node (ref "IC24") (pin "12") (pinfunction "SCL_12") (pintype "input"))
      (node (ref "IC42") (pin "22") (pinfunction "SCL_22") (pintype "input"))
      (node (ref "R228") (pin "2") (pinfunction "2_2") (pintype "passive"))
    )
    (net (code "22") (name "/GPIO_SDA0") (class "Default")
      (node (ref "IC25") (pin "13") (pinfunction "SDA_13") (pintype "bidirectional"))
      (node (ref "IC43") (pin "23") (pinfunction "SDA_23") (pintype "bidirectional"))
      (node (ref "R233") (pin "2") (pinfunction "2_2") (pintype "passive"))
    )
    (net (code "23") (name "/GPIO_SDA1") (class "Default")
      (node (ref "IC24") (pin "13") (pinfunction "SDA_13") (pintype "bidirectional"))
      (node (ref "IC42") (pin "23") (pinfunction "SDA_23") (pintype "bidirectional"))
      (node (ref "R232") (pin "2") (pinfunction "2_2") (pintype "passive"))
    )
    (net (code "24") (name "/HW_REV0") (class "Default")
      (node (ref "R118") (pin "1") (pinfunction "1_1") (pintype "passive"))
    )
    (net (code "25") (name "/HW_REV1") (class "Default")
      (node (ref "R119") (pin "1") (pinfunction "1_1") (pintype "passive"))
    )
    (net (code "26") (name "/HW_REV2") (class "Default")
      (node (ref "R120") (pin "1") (pinfunction "1_1") (pintype "passive"))
    )
    (net (code "27") (name "/HW_REV3") (class "Default")
      (node (ref "R121") (pin "1") (pinfunction "1_1") (pintype "passive"))
    )
    (net (code "28") (name "/I2C_1V8_SW_SCL") (class "Default")
      (node (ref "IC13") (pin "3") (pinfunction "SCL1_3") (pintype "bidirectional"))
      (node (ref "R147") (pin "1") (pinfunction "1_1") (pintype "passive"))
      (node (ref "TP14") (pin "1") (pinfunction "1_1") (pintype "bidirectional"))
    )
    (net (code "29") (name "/I2C_1V8_SW_SDA") (class "Default")
      (node (ref "IC13") (pin "4") (pinfunction "SDA1_4") (pintype "bidirectional"))
      (node (ref "R146") (pin "1") (pinfunction "1_1") (pintype "passive"))
      (node (ref "TP13") (pin "1") (pinfunction "1_1") (pintype "bidirectional"))
    )
    (net (code "30") (name "/I2C_3V3_SW_SCL") (class "Default")
      (node (ref "IC13") (pin "6") (pinfunction "SCL2_6") (pintype "bidirectional"))
      (node (ref "IC14") (pin "19") (pinfunction "SCL_19") (pintype "bidirectional"))
      (node (ref "IC15") (pin "19") (pinfunction "SCL_19") (pintype "bidirectional"))
      (node (ref "R149") (pin "1") (pinfunction "1_1") (pintype "passive"))
    )
    (net (code "31") (name "/I2C_3V3_SW_SDA") (class "Default")
      (node (ref "IC13") (pin "5") (pinfunction "SDA2_5") (pintype "bidirectional"))
      (node (ref "IC14") (pin "20") (pinfunction "SDA_20") (pintype "bidirectional"))
      (node (ref "IC15") (pin "20") (pinfunction "SDA_20") (pintype "bidirectional"))
      (node (ref "R148") (pin "1") (pinfunction "1_1") (pintype "passive"))
    )
    (net (code "32") (name "/I2C_SCL_0") (class "Default")
      (node (ref "IC14") (pin "17") (pinfunction "SC7_17") (pintype "bidirectional"))
      (node (ref "R156") (pin "1") (pinfunction "1_1") (pintype "passive"))
    )
    (net (code "33") (name "/I2C_SCL_1") (class "Default")
      (node (ref "IC14") (pin "13") (pinfunction "SC5_13") (pintype "bidirectional"))
      (node (ref "R158") (pin "1") (pinfunction "1_1") (pintype "passive"))
    )
    (net (code "34") (name "/I2C_SCL_2") (class "Default")
      (node (ref "IC14") (pin "11") (pinfunction "SC4_11") (pintype "bidirectional"))
      (node (ref "R160") (pin "1") (pinfunction "1_1") (pintype "passive"))
    )
    (net (code "35") (name "/I2C_SCL_3") (class "Default")
      (node (ref "IC14") (pin "8") (pinfunction "SC3_8") (pintype "bidirectional"))
      (node (ref "R162") (pin "1") (pinfunction "1_1") (pintype "passive"))
    )
    (net (code "36") (name "/I2C_SCL_4") (class "Default")
      (node (ref "IC14") (pin "6") (pinfunction "SC2_6") (pintype "bidirectional"))
      (node (ref "R164") (pin "1") (pinfunction "1_1") (pintype "passive"))
    )
    (net (code "37") (name "/I2C_SCL_5") (class "Default")
      (node (ref "IC14") (pin "4") (pinfunction "SC1_4") (pintype "bidirectional"))
      (node (ref "R166") (pin "1") (pinfunction "1_1") (pintype "passive"))
    )
    (net (code "38") (name "/I2C_SCL_6") (class "Default")
      (node (ref "IC14") (pin "2") (pinfunction "SC0_2") (pintype "bidirectional"))
      (node (ref "R168") (pin "1") (pinfunction "1_1") (pintype "passive"))
    )
    (net (code "39") (name "/I2C_SCL_7") (class "Default")
      (node (ref "IC14") (pin "15") (pinfunction "SC6_15") (pintype "bidirectional"))
      (node (ref "R170") (pin "1") (pinfunction "1_1") (pintype "passive"))
    )
    (net (code "40") (name "/I2C_SCL_8") (class "Default")
      (node (ref "IC15") (pin "11") (pinfunction "SC4_11") (pintype "bidirectional"))
      (node (ref "R172") (pin "1") (pinfunction "1_1") (pintype "passive"))
    )
    (net (code "41") (name "/I2C_SCL_9") (class "Default")
      (node (ref "IC15") (pin "13") (pinfunction "SC5_13") (pintype "bidirectional"))
      (node (ref "R175") (pin "1") (pinfunction "1_1") (pintype "passive"))
    )
    (net (code "42") (name "/I2C_SCL_10") (class "Default")
      (node (ref "IC15") (pin "17") (pinfunction "SC7_17") (pintype "bidirectional"))
      (node (ref "R178") (pin "1") (pinfunction "1_1") (pintype "passive"))
    )
    (net (code "43") (name "/I2C_SCL_11") (class "Default")
      (node (ref "IC15") (pin "15") (pinfunction "SC6_15") (pintype "bidirectional"))
      (node (ref "R182") (pin "1") (pinfunction "1_1") (pintype "passive"))
    )
    (net (code "45") (name "/I2C_SDA_0") (class "Default")
      (node (ref "IC14") (pin "16") (pinfunction "SD7_16") (pintype "bidirectional"))
      (node (ref "R155") (pin "1") (pinfunction "1_1") (pintype "passive"))
    )
    (net (code "46") (name "/I2C_SDA_1") (class "Default")
      (node (ref "IC14") (pin "12") (pinfunction "SD5_12") (pintype "bidirectional"))
      (node (ref "R157") (pin "1") (pinfunction "1_1") (pintype "passive"))
    )
    (net (code "47") (name "/I2C_SDA_2") (class "Default")
      (node (ref "IC14") (pin "10") (pinfunction "SD4_10") (pintype "bidirectional"))
      (node (ref "R159") (pin "1") (pinfunction "1_1") (pintype "passive"))
    )
    (net (code "48") (name "/I2C_SDA_3") (class "Default")
      (node (ref "IC14") (pin "7") (pinfunction "SD3_7") (pintype "bidirectional"))
      (node (ref "R161") (pin "1") (pinfunction "1_1") (pintype "passive"))
    )
    (net (code "49") (name "/I2C_SDA_4") (class "Default")
      (node (ref "IC14") (pin "5") (pinfunction "SD2_5") (pintype "bidirectional"))
      (node (ref "R163") (pin "1") (pinfunction "1_1") (pintype "passive"))
    )
    (net (code "50") (name "/I2C_SDA_5") (class "Default")
      (node (ref "IC14") (pin "3") (pinfunction "SD1_3") (pintype "bidirectional"))
      (node (ref "R165") (pin "1") (pinfunction "1_1") (pintype "passive"))
    )
    (net (code "51") (name "/I2C_SDA_6") (class "Default")
      (node (ref "IC14") (pin "1") (pinfunction "SD0_1") (pintype "bidirectional"))
      (node (ref "R167") (pin "1") (pinfunction "1_1") (pintype "passive"))
    )
    (net (code "52") (name "/I2C_SDA_7") (class "Default")
      (node (ref "IC14") (pin "14") (pinfunction "SD6_14") (pintype "bidirectional"))
      (node (ref "R169") (pin "1") (pinfunction "1_1") (pintype "passive"))
    )
    (net (code "53") (name "/I2C_SDA_8") (class "Default")
      (node (ref "IC15") (pin "10") (pinfunction "SD4_10") (pintype "bidirectional"))
      (node (ref "R171") (pin "1") (pinfunction "1_1") (pintype "passive"))
    )
    (net (code "54") (name "/I2C_SDA_9") (class "Default")
      (node (ref "IC15") (pin "12") (pinfunction "SD5_12") (pintype "bidirectional"))
      (node (ref "R173") (pin "1") (pinfunction "1_1") (pintype "passive"))
    )
    (net (code "55") (name "/I2C_SDA_10") (class "Default")
      (node (ref "IC15") (pin "16") (pinfunction "SD7_16") (pintype "bidirectional"))
      (node (ref "R176") (pin "1") (pinfunction "1_1") (pintype "passive"))
    )
    (net (code "56") (name "/I2C_SDA_11") (class "Default")
      (node (ref "IC15") (pin "14") (pinfunction "SD6_14") (pintype "bidirectional"))
      (node (ref "R180") (pin "1") (pinfunction "1_1") (pintype "passive"))
    )
    (net (code "58") (name "/I2C_SW_RESET") (class "Default")
      (node (ref "R33") (pin "2") (pinfunction "2_2") (pintype "passive"))
      (node (ref "T21") (pin "1") (pinfunction "G_1") (pintype "passive"))
    )
    (net (code "59") (name "/I2C_SW_RESET2") (class "Default")
      (node (ref "R46") (pin "2") (pinfunction "2_2") (pintype "passive"))
      (node (ref "T22") (pin "1") (pinfunction "G_1") (pintype "passive"))
    )
    (net (code "60") (name "/I2C_SW_RESET_N") (class "Default")
      (node (ref "IC14") (pin "24") (pinfunction "~{RESET}_24") (pintype "input"))
      (node (ref "IC15") (pin "24") (pinfunction "~{RESET}_24") (pintype "input"))
      (node (ref "R151") (pin "1") (pinfunction "1_1") (pintype "passive"))
      (node (ref "T21") (pin "3") (pinfunction "D_3") (pintype "passive"))
      (node (ref "T22") (pin "3") (pinfunction "D_3") (pintype "passive"))
    )
    (net (code "61") (name "/SFP_0.LED") (class "Default")
      (node (ref "IC25") (pin "28") (pinfunction "GPA7_28") (pintype "bidirectional"))
      (node (ref "IC43") (pin "11") (pinfunction "P0_7_11") (pintype "bidirectional"))
    )
    (net (code "62") (name "/SFP_0.LOS") (class "Default")
      (node (ref "IC25") (pin "26") (pinfunction "GPA5_26") (pintype "bidirectional"))
      (node (ref "IC43") (pin "9") (pinfunction "P0_5_9") (pintype "bidirectional"))
    )
    (net (code "63") (name "/SFP_0.MOD_PRESENT") (class "Default")
      (node (ref "IC25") (pin "25") (pinfunction "GPA4_25") (pintype "bidirectional"))
      (node (ref "IC43") (pin "8") (pinfunction "P0_4_8") (pintype "bidirectional"))
    )
    (net (code "64") (name "/SFP_0.RATE_SELECT") (class "Default")
      (node (ref "IC25") (pin "24") (pinfunction "GPA3_24") (pintype "bidirectional"))
      (node (ref "IC43") (pin "7") (pinfunction "P0_3_7") (pintype "bidirectional"))
    )
    (net (code "65") (name "/SFP_0.RATE_SELECT1") (class "Default")
      (node (ref "IC25") (pin "23") (pinfunction "GPA2_23") (pintype "bidirectional"))
      (node (ref "IC43") (pin "6") (pinfunction "P0_2_6") (pintype "bidirectional"))
    )
    (net (code "66") (name "/SFP_0.SCL") (class "Default")
      (node (ref "IC15") (pin "2") (pinfunction "SC0_2") (pintype "bidirectional"))
      (node (ref "R184") (pin "1") (pinfunction "1_1") (pintype "passive"))
    )
    (net (code "67") (name "/SFP_0.SDA") (class "Default")
      (node (ref "IC15") (pin "1") (pinfunction "SD0_1") (pintype "bidirectional"))
      (node (ref "R183") (pin "1") (pinfunction "1_1") (pintype "passive"))
    )
    (net (code "68") (name "/SFP_0.TX_DISABLE") (class "Default")
      (node (ref "IC25") (pin "22") (pinfunction "GPA1_22") (pintype "bidirectional"))
      (node (ref "IC43") (pin "5") (pinfunction "P0_1_5") (pintype "bidirectional"))
    )
    (net (code "69") (name "/SFP_0.TX_FAULT") (class "Default")
      (node (ref "IC25") (pin "21") (pinfunction "GPA0_21") (pintype "bidirectional"))
      (node (ref "IC43") (pin "4") (pinfunction "P0_0_4") (pintype "bidirectional"))
    )
    (net (code "71") (name "/SFP_1.LED") (class "Default")
      (node (ref "IC25") (pin "7") (pinfunction "GPB6_7") (pintype "bidirectional"))
      (node (ref "IC43") (pin "19") (pinfunction "P1_6_19") (pintype "bidirectional"))
    )
    (net (code "72") (name "/SFP_1.LOS") (class "Default")
      (node (ref "IC25") (pin "6") (pinfunction "GPB5_6") (pintype "bidirectional"))
      (node (ref "IC43") (pin "18") (pinfunction "P1_5_18") (pintype "bidirectional"))
    )
    (net (code "73") (name "/SFP_1.MOD_PRESENT") (class "Default")
      (node (ref "IC25") (pin "5") (pinfunction "GPB4_5") (pintype "bidirectional"))
      (node (ref "IC43") (pin "17") (pinfunction "P1_4_17") (pintype "bidirectional"))
    )
    (net (code "74") (name "/SFP_1.RATE_SELECT") (class "Default")
      (node (ref "IC25") (pin "4") (pinfunction "GPB3_4") (pintype "bidirectional"))
      (node (ref "IC43") (pin "16") (pinfunction "P1_3_16") (pintype "bidirectional"))
    )
    (net (code "75") (name "/SFP_1.RATE_SELECT1") (class "Default")
      (node (ref "IC25") (pin "3") (pinfunction "GPB2_3") (pintype "bidirectional"))
      (node (ref "IC43") (pin "15") (pinfunction "P1_2_15") (pintype "bidirectional"))
    )
    (net (code "76") (name "/SFP_1.SCL") (class "Default")
      (node (ref "IC15") (pin "4") (pinfunction "SC1_4") (pintype "bidirectional"))
      (node (ref "R186") (pin "1") (pinfunction "1_1") (pintype "passive"))
    )
    (net (code "77") (name "/SFP_1.SDA") (class "Default")
      (node (ref "IC15") (pin "3") (pinfunction "SD1_3") (pintype "bidirectional"))
      (node (ref "R185") (pin "1") (pinfunction "1_1") (pintype "passive"))
    )
    (net (code "78") (name "/SFP_1.TX_DISABLE") (class "Default")
      (node (ref "IC25") (pin "2") (pinfunction "GPB1_2") (pintype "bidirectional"))
      (node (ref "IC43") (pin "14") (pinfunction "P1_1_14") (pintype "bidirectional"))
    )
    (net (code "79") (name "/SFP_1.TX_FAULT") (class "Default")
      (node (ref "IC25") (pin "1") (pinfunction "GPB0_1") (pintype "bidirectional"))
      (node (ref "IC43") (pin "13") (pinfunction "P1_0_13") (pintype "bidirectional"))
    )
    (net (code "81") (name "/SFP_2.LED") (class "Default")
      (node (ref "IC24") (pin "27") (pinfunction "GPA6_27") (pintype "bidirectional"))
      (node (ref "IC42") (pin "10") (pinfunction "P0_6_10") (pintype "bidirectional"))
    )
    (net (code "82") (name "/SFP_2.LOS") (class "Default")
      (node (ref "IC24") (pin "26") (pinfunction "GPA5_26") (pintype "bidirectional"))
      (node (ref "IC42") (pin "9") (pinfunction "P0_5_9") (pintype "bidirectional"))
    )
    (net (code "83") (name "/SFP_2.MOD_PRESENT") (class "Default")
      (node (ref "IC24") (pin "25") (pinfunction "GPA4_25") (pintype "bidirectional"))
      (node (ref "IC42") (pin "8") (pinfunction "P0_4_8") (pintype "bidirectional"))
    )
    (net (code "84") (name "/SFP_2.RATE_SELECT") (class "Default")
      (node (ref "IC24") (pin "24") (pinfunction "GPA3_24") (pintype "bidirectional"))
      (node (ref "IC42") (pin "7") (pinfunction "P0_3_7") (pintype "bidirectional"))
    )
    (net (code "85") (name "/SFP_2.RATE_SELECT1") (class "Default")
      (node (ref "IC24") (pin "23") (pinfunction "GPA2_23") (pintype "bidirectional"))
      (node (ref "IC42") (pin "6") (pinfunction "P0_2_6") (pintype "bidirectional"))
    )
    (net (code "86") (name "/SFP_2.SCL") (class "Default")
      (node (ref "IC15") (pin "6") (pinfunction "SC2_6") (pintype "bidirectional"))
      (node (ref "R188") (pin "1") (pinfunction "1_1") (pintype "passive"))
    )
    (net (code "87") (name "/SFP_2.SDA") (class "Default")
      (node (ref "IC15") (pin "5") (pinfunction "SD2_5") (pintype "bidirectional"))
      (node (ref "R187") (pin "1") (pinfunction "1_1") (pintype "passive"))
    )
    (net (code "88") (name "/SFP_2.TX_DISABLE") (class "Default")
      (node (ref "IC24") (pin "22") (pinfunction "GPA1_22") (pintype "bidirectional"))
      (node (ref "IC42") (pin "5") (pinfunction "P0_1_5") (pintype "bidirectional"))
    )
    (net (code "89") (name "/SFP_2.TX_FAULT") (class "Default")
      (node (ref "IC24") (pin "21") (pinfunction "GPA0_21") (pintype "bidirectional"))
      (node (ref "IC42") (pin "4") (pinfunction "P0_0_4") (pintype "bidirectional"))
    )
    (net (code "91") (name "/SFP_3.LED") (class "Default")
      (node (ref "IC24") (pin "7") (pinfunction "GPB6_7") (pintype "bidirectional"))
      (node (ref "IC42") (pin "19") (pinfunction "P1_6_19") (pintype "bidirectional"))
    )
    (net (code "92") (name "/SFP_3.LOS") (class "Default")
      (node (ref "IC24") (pin "6") (pinfunction "GPB5_6") (pintype "bidirectional"))
      (node (ref "IC42") (pin "18") (pinfunction "P1_5_18") (pintype "bidirectional"))
    )
    (net (code "93") (name "/SFP_3.MOD_PRESENT") (class "Default")
      (node (ref "IC24") (pin "5") (pinfunction "GPB4_5") (pintype "bidirectional"))
      (node (ref "IC42") (pin "17") (pinfunction "P1_4_17") (pintype "bidirectional"))
    )
    (net (code "94") (name "/SFP_3.RATE_SELECT") (class "Default")
      (node (ref "IC24") (pin "4") (pinfunction "GPB3_4") (pintype "bidirectional"))
      (node (ref "IC42") (pin "16") (pinfunction "P1_3_16") (pintype "bidirectional"))
    )
    (net (code "95") (name "/SFP_3.RATE_SELECT1") (class "Default")
      (node (ref "IC24") (pin "3") (pinfunction "GPB2_3") (pintype "bidirectional"))
      (node (ref "IC42") (pin "15") (pinfunction "P1_2_15") (pintype "bidirectional"))
    )
    (net (code "96") (name "/SFP_3.TX_DISABLE") (class "Default")
      (node (ref "IC24") (pin "2") (pinfunction "GPB1_2") (pintype "bidirectional"))
      (node (ref "IC42") (pin "14") (pinfunction "P1_1_14") (pintype "bidirectional"))
    )
    (net (code "97") (name "/SFP_3.TX_FAULT") (class "Default")
      (node (ref "IC24") (pin "1") (pinfunction "GPB0_1") (pintype "bidirectional"))
      (node (ref "IC42") (pin "13") (pinfunction "P1_0_13") (pintype "bidirectional"))
    )
    (net (code "99") (name "/SHARED_SCL") (class "Default")
      (node (ref "IC15") (pin "8") (pinfunction "SC3_8") (pintype "bidirectional"))
      (node (ref "IC27") (pin "2") (pinfunction "SCL_2") (pintype "input"))
      (node (ref "IC28") (pin "2") (pinfunction "SCL_2") (pintype "input"))
      (node (ref "R190") (pin "1") (pinfunction "1_1") (pintype "passive"))
      (node (ref "R228") (pin "1") (pinfunction "1_1") (pintype "passive"))
      (node (ref "R229") (pin "1") (pinfunction "1_1") (pintype "passive"))
      (node (ref "R231") (pin "1") (pinfunction "1_1") (pintype "passive"))
      (node (ref "R235") (pin "1") (pinfunction "1_1") (pintype "passive"))
      (node (ref "TP3") (pin "1") (pinfunction "1_1") (pintype "bidirectional"))
    )
    (net (code "100") (name "/SHARED_SDA") (class "Default")
      (node (ref "IC15") (pin "7") (pinfunction "SD3_7") (pintype "bidirectional"))
      (node (ref "IC27") (pin "1") (pinfunction "SDA_1") (pintype "bidirectional"))
      (node (ref "IC28") (pin "1") (pinfunction "SDA_1") (pintype "bidirectional"))
      (node (ref "R189") (pin "1") (pinfunction "1_1") (pintype "passive"))
      (node (ref "R230") (pin "1") (pinfunction "1_1") (pintype "passive"))
      (node (ref "R232") (pin "1") (pinfunction "1_1") (pintype "passive"))
      (node (ref "R233") (pin "1") (pinfunction "1_1") (pintype "passive"))
      (node (ref "R234") (pin "1") (pinfunction "1_1") (pintype "passive"))
      (node (ref "TP2") (pin "1") (pinfunction "1_1") (pintype "bidirectional"))
    )
    (net (code "101") (name "/VUSB_PRESENT_N") (class "Default")
      (node (ref "IC25") (pin "27") (pinfunction "GPA6_27") (pintype "bidirectional"))
      (node (ref "IC43") (pin "10") (pinfunction "P0_6_10") (pintype "bidirectional"))
    )
    (net (code "106") (name "GND") (class "Default")
      (node (ref "C186") (pin "1") (pinfunction "1_1") (pintype "passive"))
      (node (ref "C192") (pin "1") (pinfunction "1_1") (pintype "passive"))
      (node (ref "C193") (pin "1") (pinfunction "1_1") (pintype "passive"))
      (node (ref "C196") (pin "1") (pinfunction "1_1") (pintype "passive"))
      (node (ref "C197") (pin "1") (pinfunction "1_1") (pintype "passive"))
      (node (ref "C198") (pin "1") (pinfunction "1_1") (pintype "passive"))
      (node (ref "C203") (pin "1") (pinfunction "1_1") (pintype "passive"))
      (node (ref "C227") (pin "1") (pinfunction "1_1") (pintype "passive"))
      (node (ref "C377") (pin "1") (pinfunction "1_1") (pintype "passive"))
      (node (ref "C378") (pin "1") (pinfunction "1_1") (pintype "passive"))
      (node (ref "C379") (pin "1") (pinfunction "1_1") (pintype "passive"))
      (node (ref "C61") (pin "1") (pinfunction "1_1") (pintype "passive"))
      (node (ref "C62") (pin "1") (pinfunction "1_1") (pintype "passive"))
      (node (ref "IC13") (pin "1") (pinfunction "GND_1") (pintype "power_in"))
      (node (ref "IC14") (pin "18") (pinfunction "A2_18") (pintype "input"))
      (node (ref "IC14") (pin "22") (pinfunction "A0_22") (pintype "input"))
      (node (ref "IC14") (pin "23") (pinfunction "A1_23") (pintype "input"))
      (node (ref "IC14") (pin "25") (pinfunction "EP_25") (pintype "power_in"))
      (node (ref "IC14") (pin "9") (pinfunction "GND_9") (pintype "power_in"))
      (node (ref "IC15") (pin "18") (pinfunction "A2_18") (pintype "input"))
      (node (ref "IC15") (pin "23") (pinfunction "A1_23") (pintype "input"))
      (node (ref "IC15") (pin "25") (pinfunction "EP_25") (pintype "power_in"))
      (node (ref "IC15") (pin "9") (pinfunction "GND_9") (pintype "power_in"))
      (node (ref "IC24") (pin "10") (pinfunction "VSS_10") (pintype "power_in"))
      (node (ref "IC24") (pin "16") (pinfunction "A1_16") (pintype "input"))
      (node (ref "IC24") (pin "17") (pinfunction "A2_17") (pintype "input"))
      (node (ref "IC25") (pin "10") (pinfunction "VSS_10") (pintype "power_in"))
      (node (ref "IC25") (pin "15") (pinfunction "A0_15") (pintype "input"))
      (node (ref "IC25") (pin "16") (pinfunction "A1_16") (pintype "input"))
      (node (ref "IC25") (pin "17") (pinfunction "A2_17") (pintype "input"))
      (node (ref "IC27") (pin "4") (pinfunction "GND_4") (pintype "power_in"))
      (node (ref "IC27") (pin "6") (pinfunction "A1_6") (pintype "input"))
      (node (ref "IC27") (pin "7") (pinfunction "A0_7") (pintype "input"))
      (node (ref "IC28") (pin "4") (pinfunction "GND_4") (pintype "power_in"))
      (node (ref "IC42") (pin "12") (pinfunction "GND_12") (pintype "power_in"))
      (node (ref "IC42") (pin "2") (pinfunction "A1_2") (pintype "input"))
      (node (ref "IC43") (pin "12") (pinfunction "GND_12") (pintype "power_in"))
      (node (ref "IC43") (pin "2") (pinfunction "A1_2") (pintype "input"))
      (node (ref "IC43") (pin "21") (pinfunction "A0_21") (pintype "input"))
      (node (ref "IC44") (pin "2") (pinfunction "VSS_2") (pintype "power_in"))
      (node (ref "IC44") (pin "4") (pinfunction "A1_4") (pintype "input"))
      (node (ref "IC44") (pin "5") (pinfunction "A0_5") (pintype "input"))
      (node (ref "IC45") (pin "1") (pinfunction "A0_1") (pintype "input"))
      (node (ref "IC45") (pin "2") (pinfunction "A1_2") (pintype "input"))
      (node (ref "IC45") (pin "3") (pinfunction "A2_3") (pintype "input"))
      (node (ref "IC45") (pin "4") (pinfunction "VSS_4") (pintype "power_in"))
      (node (ref "IC5") (pin "4") (pinfunction "VSS_4") (pintype "power_in"))
      (node (ref "R120") (pin "2") (pinfunction "2_2") (pintype "passive"))
      (node (ref "R121") (pin "2") (pinfunction "2_2") (pintype "passive"))
      (node (ref "R123") (pin "1") (pinfunction "1_1") (pintype "passive"))
      (node (ref "R33") (pin "1") (pinfunction "1_1") (pintype "passive"))
      (node (ref "R46") (pin "1") (pinfunction "1_1") (pintype "passive"))
      (node (ref "T21") (pin "2") (pinfunction "S_2") (pintype "passive"))
      (node (ref "T22") (pin "2") (pinfunction "S_2") (pintype "passive"))
    )
    (net (code "107") (name "Net-(IC5-SCL)") (class "Default")
      (node (ref "IC5") (pin "6") (pinfunction "SCL_6") (pintype "input"))
      (node (ref "R231") (pin "2") (pinfunction "2_2") (pintype "passive"))
    )
    (net (code "108") (name "Net-(IC5-SDA)") (class "Default")
      (node (ref "IC5") (pin "5") (pinfunction "SDA_5") (pintype "bidirectional"))
      (node (ref "R230") (pin "2") (pinfunction "2_2") (pintype "passive"))
    )
    (net (code "109") (name "Net-(IC13-EN)") (class "Default")
      (node (ref "C186") (pin "2") (pinfunction "2_2") (pintype "passive"))
      (node (ref "IC13") (pin "7") (pinfunction "VREF2_7") (pintype "input"))
      (node (ref "IC13") (pin "8") (pinfunction "EN_8") (pintype "input"))
      (node (ref "R240") (pin "1") (pinfunction "1_1") (pintype "passive"))
    )
    (net (code "110") (name "P1V8") (class "Default")
      (node (ref "C193") (pin "2") (pinfunction "2_2") (pintype "passive"))
      (node (ref "C379") (pin "2") (pinfunction "2_2") (pintype "passive"))
      (node (ref "IC13") (pin "2") (pinfunction "VREF1_2") (pintype "input"))
      (node (ref "IC44") (pin "6") (pinfunction "VCC_6") (pintype "power_in"))
      (node (ref "IC45") (pin "8") (pinfunction "VCC_8") (pintype "power_in"))
      (node (ref "R115") (pin "2") (pinfunction "2_2") (pintype "passive"))
      (node (ref "R116") (pin "2") (pinfunction "2_2") (pintype "passive"))
      (node (ref "R118") (pin "2") (pinfunction "2_2") (pintype "passive"))
      (node (ref "R119") (pin "2") (pinfunction "2_2") (pintype "passive"))
      (node (ref "R122") (pin "2") (pinfunction "2_2") (pintype "passive"))
      (node (ref "R146") (pin "2") (pinfunction "2_2") (pintype "passive"))
      (node (ref "R147") (pin "2") (pinfunction "2_2") (pintype "passive"))
    )
    (net (code "111") (name "P3V3") (class "Default")
      (node (ref "C192") (pin "2") (pinfunction "2_2") (pintype "passive"))
      (node (ref "C196") (pin "2") (pinfunction "2_2") (pintype "passive"))
      (node (ref "C197") (pin "2") (pinfunction "2_2") (pintype "passive"))
      (node (ref "C198") (pin "2") (pinfunction "2_2") (pintype "passive"))
      (node (ref "C203") (pin "2") (pinfunction "2_2") (pintype "passive"))
      (node (ref "C227") (pin "2") (pinfunction "2_2") (pintype "passive"))
      (node (ref "C377") (pin "2") (pinfunction "2_2") (pintype "passive"))
      (node (ref "C378") (pin "2") (pinfunction "2_2") (pintype "passive"))
      (node (ref "C61") (pin "2") (pinfunction "2_2") (pintype "passive"))
      (node (ref "C62") (pin "2") (pinfunction "2_2") (pintype "passive"))
      (node (ref "IC14") (pin "21") (pinfunction "VCC_21") (pintype "power_in"))
      (node (ref "IC15") (pin "21") (pinfunction "VCC_21") (pintype "power_in"))
      (node (ref "IC15") (pin "22") (pinfunction "A0_22") (pintype "input"))
      (node (ref "IC24") (pin "15") (pinfunction "A0_15") (pintype "input"))
      (node (ref "IC24") (pin "9") (pinfunction "VDD_9") (pintype "power_in"))
      (node (ref "IC25") (pin "9") (pinfunction "VDD_9") (pintype "power_in"))
      (node (ref "IC27") (pin "5") (pinfunction "A2_5") (pintype "input"))
      (node (ref "IC27") (pin "8") (pinfunction "+VS_8") (pintype "power_in"))
      (node (ref "IC28") (pin "5") (pinfunction "A2_5") (pintype "input"))
      (node (ref "IC28") (pin "6") (pinfunction "A1_6") (pintype "input"))
      (node (ref "IC28") (pin "7") (pinfunction "A0_7") (pintype "input"))
      (node (ref "IC28") (pin "8") (pinfunction "+VS_8") (pintype "power_in"))
      (node (ref "IC42") (pin "21") (pinfunction "A0_21") (pintype "input"))
      (node (ref "IC42") (pin "24") (pinfunction "VCC_24") (pintype "power_in"))
      (node (ref "IC43") (pin "24") (pinfunction "VCC_24") (pintype "power_in"))
      (node (ref "IC5") (pin "1") (pinfunction "A0_1") (pintype "input"))
      (node (ref "IC5") (pin "2") (pinfunction "A1_2") (pintype "input"))
      (node (ref "IC5") (pin "3") (pinfunction "A2_3") (pintype "input"))
      (node (ref "IC5") (pin "8") (pinfunction "VCC_8") (pintype "power_in"))
      (node (ref "R125") (pin "2") (pinfunction "2_2") (pintype "passive"))
      (node (ref "R131") (pin "1") (pinfunction "1_1") (pintype "passive"))
      (node (ref "R132") (pin "1") (pinfunction "1_1") (pintype "passive"))
      (node (ref "R148") (pin "2") (pinfunction "2_2") (pintype "passive"))
      (node (ref "R149") (pin "2") (pinfunction "2_2") (pintype "passive"))
      (node (ref "R151") (pin "2") (pinfunction "2_2") (pintype "passive"))
      (node (ref "R155") (pin "2") (pinfunction "2_2") (pintype "passive"))
      (node (ref "R156") (pin "2") (pinfunction "2_2") (pintype "passive"))
      (node (ref "R157") (pin "2") (pinfunction "2_2") (pintype "passive"))
      (node (ref "R158") (pin "2") (pinfunction "2_2") (pintype "passive"))
      (node (ref "R159") (pin "2") (pinfunction "2_2") (pintype "passive"))
      (node (ref "R160") (pin "2") (pinfunction "2_2") (pintype "passive"))
      (node (ref "R161") (pin "2") (pinfunction "2_2") (pintype "passive"))
      (node (ref "R162") (pin "2") (pinfunction "2_2") (pintype "passive"))
      (node (ref "R163") (pin "2") (pinfunction "2_2") (pintype "passive"))
      (node (ref "R164") (pin "2") (pinfunction "2_2") (pintype "passive"))
      (node (ref "R165") (pin "2") (pinfunction "2_2") (pintype "passive"))
      (node (ref "R166") (pin "2") (pinfunction "2_2") (pintype "passive"))
      (node (ref "R167") (pin "2") (pinfunction "2_2") (pintype "passive"))
      (node (ref "R168") (pin "2") (pinfunction "2_2") (pintype "passive"))
      (node (ref "R169") (pin "2") (pinfunction "2_2") (pintype "passive"))
      (node (ref "R170") (pin "2") (pinfunction "2_2") (pintype "passive"))
      (node (ref "R171") (pin "2") (pinfunction "2_2") (pintype "passive"))
      (node (ref "R172") (pin "2") (pinfunction "2_2") (pintype "passive"))
      (node (ref "R173") (pin "2") (pinfunction "2_2") (pintype "passive"))
      (node (ref "R175") (pin "2") (pinfunction "2_2") (pintype "passive"))
      (node (ref "R176") (pin "2") (pinfunction "2_2") (pintype "passive"))
      (node (ref "R178") (pin "2") (pinfunction "2_2") (pintype "passive"))
      (node (ref "R180") (pin "2") (pinfunction "2_2") (pintype "passive"))
      (node (ref "R182") (pin "2") (pinfunction "2_2") (pintype "passive"))
      (node (ref "R183") (pin "2") (pinfunction "2_2") (pintype "passive"))
      (node (ref "R184") (pin "2") (pinfunction "2_2") (pintype "passive"))
      (node (ref "R185") (pin "2") (pinfunction "2_2") (pintype "passive"))
      (node (ref "R186") (pin "2") (pinfunction "2_2") (pintype "passive"))
      (node (ref "R187") (pin "2") (pinfunction "2_2") (pintype "passive"))
      (node (ref "R188") (pin "2") (pinfunction "2_2") (pintype "passive"))
      (node (ref "R189") (pin "2") (pinfunction "2_2") (pintype "passive"))
      (node (ref "R190") (pin "2") (pinfunction "2_2") (pintype "passive"))
      (node (ref "R240") (pin "2") (pinfunction "2_2") (pintype "passive"))
    )
    (net (code "112") (name "unconnected-(IC5-NC-Pad7)") (class "Default")
      (node (ref "IC5") (pin "7") (pinfunction "NC_7") (pintype "passive+no_connect"))
    )
    (net (code "113") (name "unconnected-(IC24-INTB-Pad19)") (class "Default")
      (node (ref "IC24") (pin "19") (pinfunction "INTB_19") (pintype "output+no_connect"))
    )
    (net (code "114") (name "unconnected-(IC24-NC-Pad11)") (class "Default")
      (node (ref "IC24") (pin "11") (pinfunction "NC_11") (pintype "passive+no_connect"))
    )
    (net (code "115") (name "unconnected-(IC24-NC-Pad14)") (class "Default")
      (node (ref "IC24") (pin "14") (pinfunction "NC_14") (pintype "passive+no_connect"))
    )
    (net (code "116") (name "unconnected-(IC25-INTB-Pad19)") (class "Default")
      (node (ref "IC25") (pin "19") (pinfunction "INTB_19") (pintype "output+no_connect"))
    )
    (net (code "117") (name "unconnected-(IC25-NC-Pad11)") (class "Default")
      (node (ref "IC25") (pin "11") (pinfunction "NC_11") (pintype "passive+no_connect"))
    )
    (net (code "118") (name "unconnected-(IC25-NC-Pad14)") (class "Default")
      (node (ref "IC25") (pin "14") (pinfunction "NC_14") (pintype "passive+no_connect"))
    )
    (net (code "119") (name "unconnected-(IC27-O.S.-Pad3)") (class "Default")
      (node (ref "IC27") (pin "3") (pinfunction "O.S._3") (pintype "output"))
    )
    (net (code "120") (name "unconnected-(IC28-O.S.-Pad3)") (class "Default")
      (node (ref "IC28") (pin "3") (pinfunction "O.S._3") (pintype "output"))
    )
    (net (code "121") (name "unconnected-(IC45-NC-Pad7)") (class "Default")
      (node (ref "IC45") (pin "7") (pinfunction "NC_7") (pintype "passive+no_connect"))
    )
    (net (code "122") (name "unconnected-(R234-Pad2)") (class "Default")
      (node (ref "R234") (pin "2") (pinfunction "2_2") (pintype "passive"))
    )
    (net (code "123") (name "unconnected-(R235-Pad2)") (class "Default")
      (node (ref "R235") (pin "2") (pinfunction "2_2") (pintype "passive"))
    )
  )
)
